# dac.net
KiCad netlist of a schematic drawn in Altium Designer
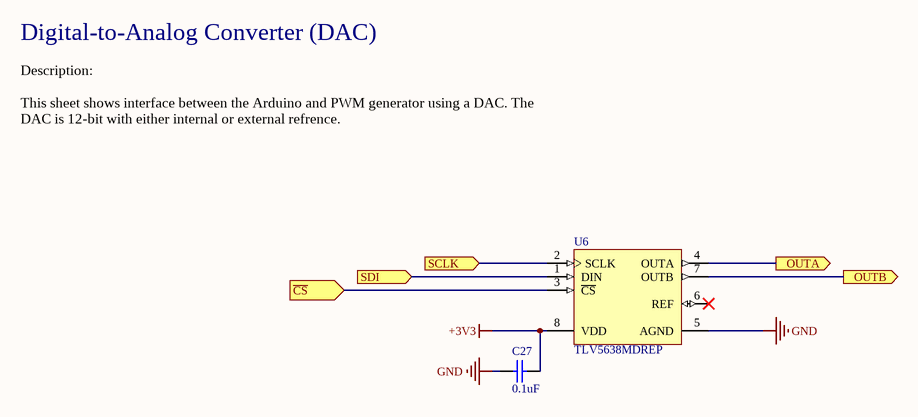
[diagram p0: dac.SchDoc]

(export (version "E")
  (design (tool "Eeschema 10.0.6"))
  (components
    (comp (ref "C27")
      (value "0.1uF")
      (footprint "CAPC1608X90X35ML10T15")
      (fields
        (field (name "TOLERANCE") "10%")
        (field (name "VOLTAGE") "50V")
        (field (name "MANUFACTURER") "Murata")
      )
      (libsource (lib "Altium Content Vault") (part "CAP-NP-2"))
    )
    (comp (ref "U6")
      (value "TLV5638MDREP")
      (footprint "TI-D8_M")
      (fields (field (name "MANUFACTURER") "Texas Instruments"))
      (libsource (lib "Altium Content Vault") (part "TI-TLV5625_26_37_38-D8"))
    )
  )
  (nets
    (net (code "1") (name "+3V3") (class "Default")
      (node (ref "C27") (pin "1") (pinfunction "1_1") (pintype "passive"))
      (node (ref "U6") (pin "8") (pinfunction "VDD_8") (pintype "power_in"))
    )
    (net (code "2") (name "/CS") (class "Default")
      (node (ref "U6") (pin "3") (pinfunction "~{CS}_3") (pintype "input"))
    )
    (net (code "3") (name "/OUTA") (class "Default")
      (node (ref "U6") (pin "4") (pinfunction "OUTA_4") (pintype "output"))
    )
    (net (code "4") (name "/OUTB") (class "Default")
      (node (ref "U6") (pin "7") (pinfunction "OUTB_7") (pintype "output"))
    )
    (net (code "5") (name "/SCLK") (class "Default")
      (node (ref "U6") (pin "2") (pinfunction "SCLK_2") (pintype "input"))
    )
    (net (code "6") (name "/SDI") (class "Default")
      (node (ref "U6") (pin "1") (pinfunction "DIN_1") (pintype "input"))
    )
    (net (code "7") (name "GND") (class "Default")
      (node (ref "C27") (pin "2") (pinfunction "2_2") (pintype "passive"))
      (node (ref "U6") (pin "5") (pinfunction "AGND_5") (pintype "power_in"))
    )
    (net (code "8") (name "unconnected-(U6-REF-Pad6)") (class "Default")
      (node (ref "U6") (pin "6") (pinfunction "REF_6") (pintype "bidirectional+no_connect"))
    )
  )
)
